# Camera-Switcher.net
KiCad netlist of a schematic drawn in EAGLE
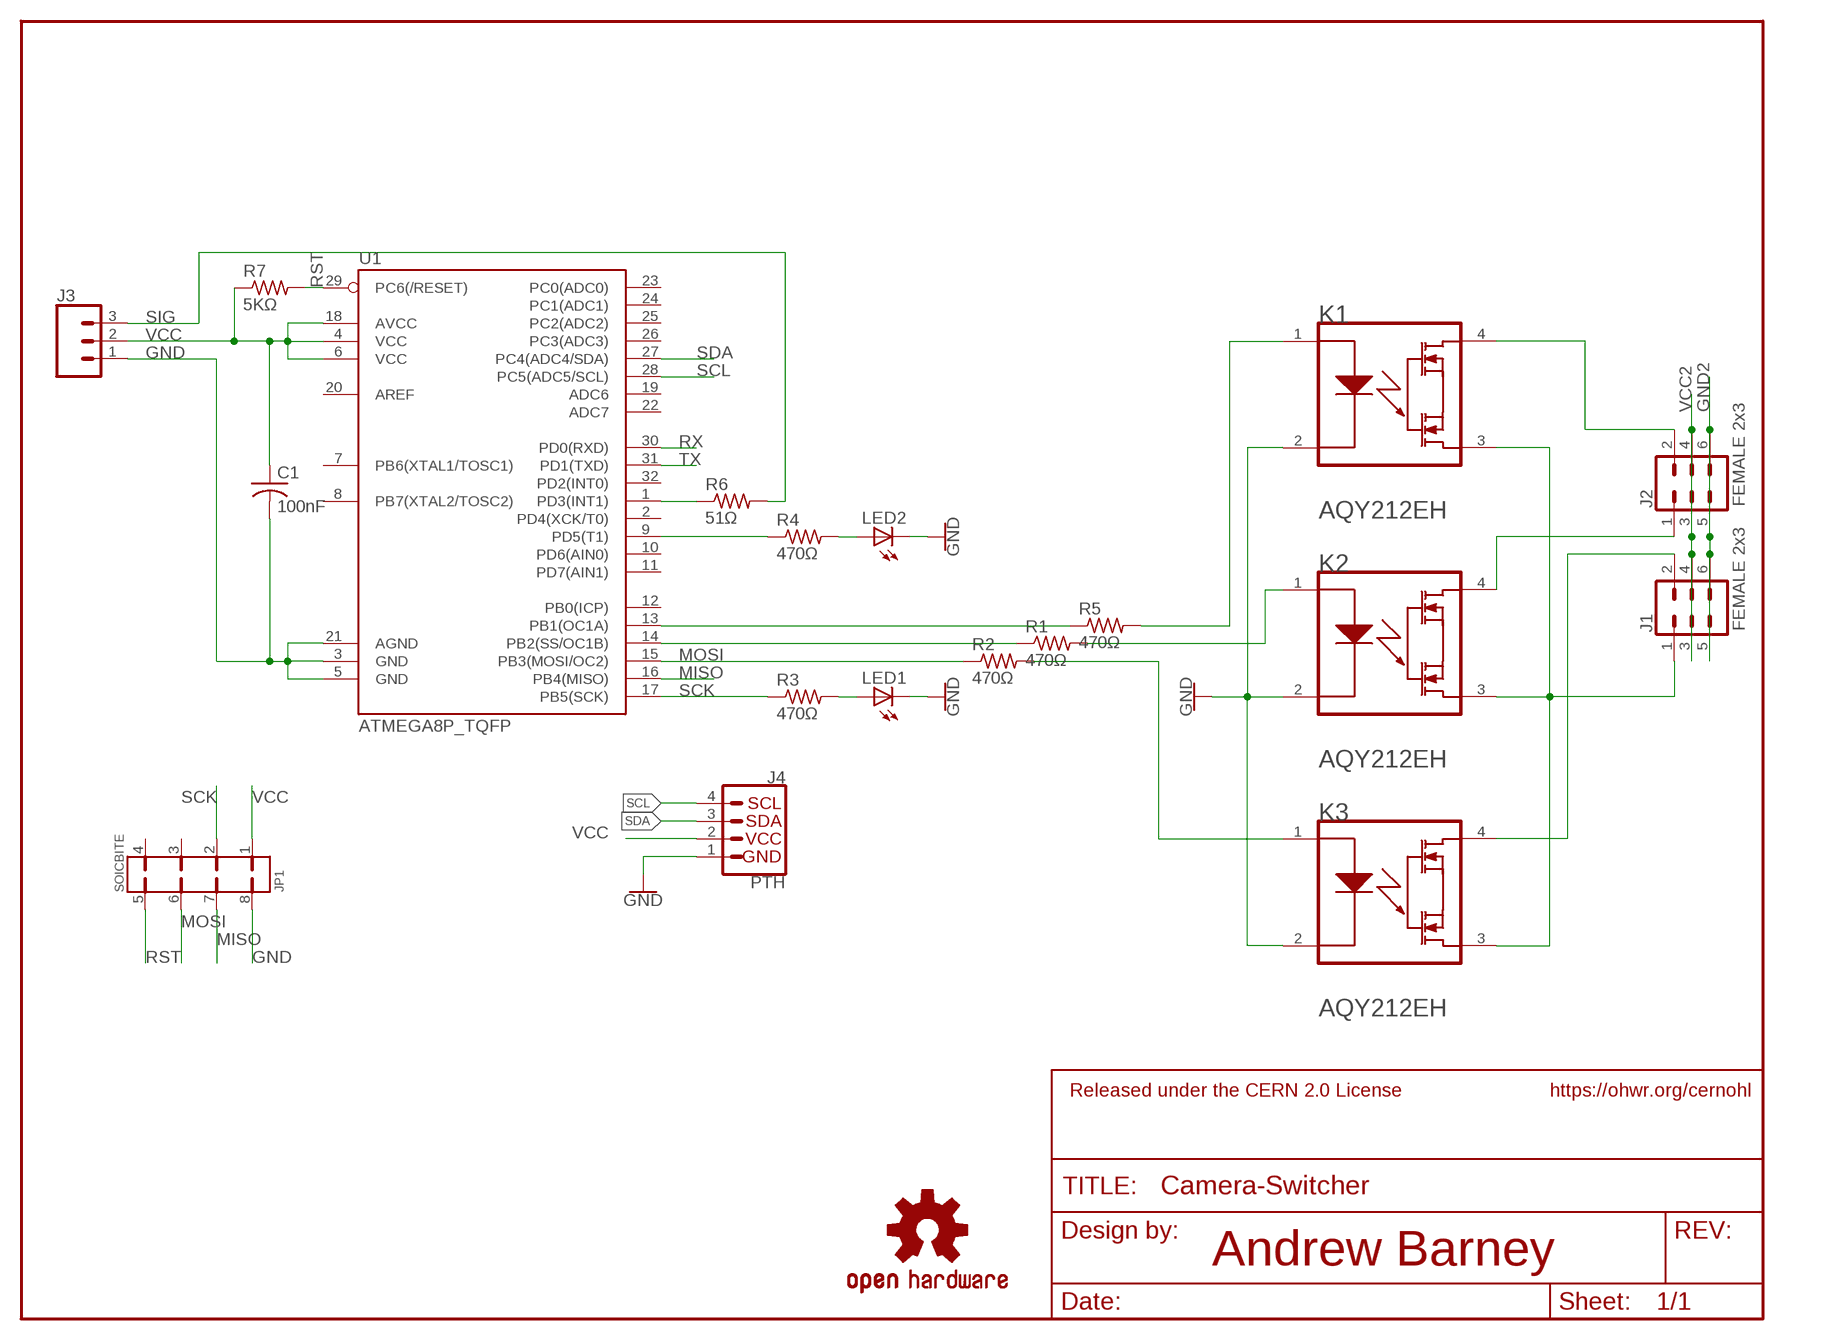
[diagram p0: schematic, sheet 1]

(export (version "E")
  (design (tool "Eeschema 10.0.6"))
  (components
    (comp (ref "C1")
      (value "100nF")
      (footprint "eagle-import:C0805")
      (libsource (lib "eagle-import") (part "C-USC0805"))
    )
    (comp (ref "FRAME1")
      (value "FRAME-LETTER-CERN\"")
      (footprint "eagle-import:CERN-OHL-S")
      (libsource (lib "eagle-import") (part "FRAME-LETTER-CERN{dblquote}"))
    )
    (comp (ref "J1")
      (value "FEMALE 2x3")
      (footprint "eagle-import:2X3")
      (libsource (lib "eagle-import") (part "CONN_03X2FEMALE"))
    )
    (comp (ref "J2")
      (value "FEMALE 2x3")
      (footprint "eagle-import:2X3")
      (libsource (lib "eagle-import") (part "CONN_03X2FEMALE"))
    )
    (comp (ref "J3")
      (value "CONN_03")
      (footprint "eagle-import:1X03")
      (libsource (lib "eagle-import") (part "CONN_03"))
    )
    (comp (ref "J4")
      (value "PTH")
      (footprint "eagle-import:1X04")
      (libsource (lib "eagle-import") (part "I2C_STANDARD"))
    )
    (comp (ref "JP1")
      (value "SOICBITE")
      (footprint "eagle-import:SOICBITE2")
      (libsource (lib "eagle-import") (part "SOICBITE2"))
    )
    (comp (ref "K1")
      (value "PANASONIC_AQY212EHPANASONIC_AQY212EH_0_0")
      (footprint "eagle-import:PANASONIC_AQY212EH_0")
      (fields (field (name "MF") "Panasonic") (field (name "MPN") "AQY212EH"))
      (libsource (lib "eagle-import") (part "PANASONIC_AQY212EHPANASONIC_AQY212EH_0_0"))
    )
    (comp (ref "K2")
      (value "PANASONIC_AQY212EHPANASONIC_AQY212EH_0_0")
      (footprint "eagle-import:PANASONIC_AQY212EH_0")
      (fields (field (name "MF") "Panasonic") (field (name "MPN") "AQY212EH"))
      (libsource (lib "eagle-import") (part "PANASONIC_AQY212EHPANASONIC_AQY212EH_0_0"))
    )
    (comp (ref "K3")
      (value "PANASONIC_AQY212EHPANASONIC_AQY212EH_0_0")
      (footprint "eagle-import:PANASONIC_AQY212EH_0")
      (fields (field (name "MF") "Panasonic") (field (name "MPN") "AQY212EH"))
      (libsource (lib "eagle-import") (part "PANASONIC_AQY212EHPANASONIC_AQY212EH_0_0"))
    )
    (comp (ref "LED1")
      (value "LEDCHIPLED_0805")
      (footprint "eagle-import:CHIPLED_0805")
      (libsource (lib "eagle-import") (part "LEDCHIPLED_0805"))
    )
    (comp (ref "LED2")
      (value "LEDCHIPLED_0805")
      (footprint "eagle-import:CHIPLED_0805")
      (libsource (lib "eagle-import") (part "LEDCHIPLED_0805"))
    )
    (comp (ref "LOGO1")
      (value "OSHW-LOGOS")
      (footprint "eagle-import:OSHW-LOGO-S")
      (libsource (lib "eagle-import") (part "OSHW-LOGOS"))
    )
    (comp (ref "R1")
      (value "470Ω")
      (footprint "eagle-import:R0805")
      (libsource (lib "eagle-import") (part "R-US_R0805"))
    )
    (comp (ref "R2")
      (value "470Ω")
      (footprint "eagle-import:R0805")
      (libsource (lib "eagle-import") (part "R-US_R0805"))
    )
    (comp (ref "R3")
      (value "470Ω")
      (footprint "eagle-import:R0805")
      (libsource (lib "eagle-import") (part "R-US_R0805"))
    )
    (comp (ref "R4")
      (value "470Ω")
      (footprint "eagle-import:R0805")
      (libsource (lib "eagle-import") (part "R-US_R0805"))
    )
    (comp (ref "R5")
      (value "470Ω")
      (footprint "eagle-import:R0805")
      (libsource (lib "eagle-import") (part "R-US_R0805"))
    )
    (comp (ref "R6")
      (value "51Ω")
      (footprint "eagle-import:R0805")
      (libsource (lib "eagle-import") (part "R-US_R0805"))
    )
    (comp (ref "R7")
      (value "5KΩ")
      (footprint "eagle-import:R0805")
      (libsource (lib "eagle-import") (part "R-US_R0805"))
    )
    (comp (ref "U1")
      (value "ATMEGA8P_TQFP")
      (footprint "eagle-import:TQFP32-08")
      (libsource (lib "eagle-import") (part "ATMEGA328P_TQFP"))
    )
  )
  (nets
    (net (code "1") (name "/GND2") (class "Default")
      (node (ref "J1") (pin "5") (pinfunction "5_5") (pintype "bidirectional"))
      (node (ref "J1") (pin "6") (pinfunction "6_6") (pintype "bidirectional"))
      (node (ref "J2") (pin "5") (pinfunction "5_5") (pintype "bidirectional"))
      (node (ref "J2") (pin "6") (pinfunction "6_6") (pintype "bidirectional"))
    )
    (net (code "2") (name "/MISO") (class "Default")
      (node (ref "JP1") (pin "7") (pinfunction "P$7_7") (pintype "passive"))
      (node (ref "U1") (pin "16") (pinfunction "PB4(MISO)_16") (pintype "bidirectional"))
    )
    (net (code "3") (name "/MOSI") (class "Default")
      (node (ref "JP1") (pin "6") (pinfunction "P$6_6") (pintype "passive"))
      (node (ref "R2") (pin "1") (pinfunction "1_1") (pintype "passive"))
      (node (ref "U1") (pin "15") (pinfunction "PB3(MOSI/OC2)_15") (pintype "bidirectional"))
    )
    (net (code "4") (name "/RST") (class "Default")
      (node (ref "JP1") (pin "5") (pinfunction "P$5_5") (pintype "passive"))
      (node (ref "R7") (pin "2") (pinfunction "2_2") (pintype "passive"))
      (node (ref "U1") (pin "29") (pinfunction "PC6(/RESET)_29") (pintype "bidirectional"))
    )
    (net (code "5") (name "/RX") (class "Default")
      (node (ref "U1") (pin "30") (pinfunction "PD0(RXD)_30") (pintype "bidirectional"))
    )
    (net (code "6") (name "/SCK") (class "Default")
      (node (ref "JP1") (pin "2") (pinfunction "P$2_2") (pintype "passive"))
      (node (ref "R3") (pin "1") (pinfunction "1_1") (pintype "passive"))
      (node (ref "U1") (pin "17") (pinfunction "PB5(SCK)_17") (pintype "bidirectional"))
    )
    (net (code "7") (name "/SIG") (class "Default")
      (node (ref "J3") (pin "3") (pinfunction "3_3") (pintype "passive"))
      (node (ref "R6") (pin "2") (pinfunction "2_2") (pintype "passive"))
    )
    (net (code "8") (name "/TX") (class "Default")
      (node (ref "U1") (pin "31") (pinfunction "PD1(TXD)_31") (pintype "bidirectional"))
    )
    (net (code "9") (name "/VCC") (class "Default")
      (node (ref "C1") (pin "1") (pinfunction "1_1") (pintype "passive"))
      (node (ref "J3") (pin "2") (pinfunction "2_2") (pintype "passive"))
      (node (ref "J4") (pin "2") (pinfunction "2_2") (pintype "power_in"))
      (node (ref "JP1") (pin "1") (pinfunction "P$1_1") (pintype "passive"))
      (node (ref "R7") (pin "1") (pinfunction "1_1") (pintype "passive"))
      (node (ref "U1") (pin "18") (pinfunction "AVCC_18") (pintype "bidirectional"))
      (node (ref "U1") (pin "4") (pinfunction "VCC_4") (pintype "bidirectional"))
      (node (ref "U1") (pin "6") (pinfunction "VCC_6") (pintype "bidirectional"))
    )
    (net (code "10") (name "/VCC2") (class "Default")
      (node (ref "J1") (pin "3") (pinfunction "3_3") (pintype "bidirectional"))
      (node (ref "J1") (pin "4") (pinfunction "4_4") (pintype "bidirectional"))
      (node (ref "J2") (pin "3") (pinfunction "3_3") (pintype "bidirectional"))
      (node (ref "J2") (pin "4") (pinfunction "4_4") (pintype "bidirectional"))
    )
    (net (code "11") (name "GND") (class "Default")
      (node (ref "C1") (pin "2") (pinfunction "2_2") (pintype "passive"))
      (node (ref "J3") (pin "1") (pinfunction "1_1") (pintype "passive"))
      (node (ref "J4") (pin "1") (pinfunction "1_1") (pintype "power_in"))
      (node (ref "JP1") (pin "8") (pinfunction "P$8_8") (pintype "passive"))
      (node (ref "K1") (pin "2") (pinfunction "2_2") (pintype "passive"))
      (node (ref "K2") (pin "2") (pinfunction "2_2") (pintype "passive"))
      (node (ref "K3") (pin "2") (pinfunction "2_2") (pintype "passive"))
      (node (ref "LED1") (pin "C") (pinfunction "C_C") (pintype "passive"))
      (node (ref "LED2") (pin "C") (pinfunction "C_C") (pintype "passive"))
      (node (ref "U1") (pin "21") (pinfunction "AGND_21") (pintype "bidirectional"))
      (node (ref "U1") (pin "3") (pinfunction "GND_3") (pintype "bidirectional"))
      (node (ref "U1") (pin "5") (pinfunction "GND_5") (pintype "bidirectional"))
    )
    (net (code "12") (name "Net-(J1-Pad1)") (class "Default")
      (node (ref "J1") (pin "1") (pinfunction "1_1") (pintype "bidirectional"))
      (node (ref "K1") (pin "3") (pinfunction "3_3") (pintype "passive"))
      (node (ref "K2") (pin "3") (pinfunction "3_3") (pintype "passive"))
      (node (ref "K3") (pin "3") (pinfunction "3_3") (pintype "passive"))
    )
    (net (code "13") (name "Net-(J1-Pad2)") (class "Default")
      (node (ref "J1") (pin "2") (pinfunction "2_2") (pintype "bidirectional"))
      (node (ref "K3") (pin "4") (pinfunction "4_4") (pintype "passive"))
    )
    (net (code "14") (name "Net-(J2-Pad1)") (class "Default")
      (node (ref "J2") (pin "1") (pinfunction "1_1") (pintype "bidirectional"))
      (node (ref "K2") (pin "4") (pinfunction "4_4") (pintype "passive"))
    )
    (net (code "15") (name "Net-(J2-Pad2)") (class "Default")
      (node (ref "J2") (pin "2") (pinfunction "2_2") (pintype "bidirectional"))
      (node (ref "K1") (pin "4") (pinfunction "4_4") (pintype "passive"))
    )
    (net (code "16") (name "Net-(K1-Pad1)") (class "Default")
      (node (ref "K1") (pin "1") (pinfunction "1_1") (pintype "passive"))
      (node (ref "R5") (pin "2") (pinfunction "2_2") (pintype "passive"))
    )
    (net (code "17") (name "Net-(K2-Pad1)") (class "Default")
      (node (ref "K2") (pin "1") (pinfunction "1_1") (pintype "passive"))
      (node (ref "R1") (pin "2") (pinfunction "2_2") (pintype "passive"))
    )
    (net (code "18") (name "Net-(K3-Pad1)") (class "Default")
      (node (ref "K3") (pin "1") (pinfunction "1_1") (pintype "passive"))
      (node (ref "R2") (pin "2") (pinfunction "2_2") (pintype "passive"))
    )
    (net (code "19") (name "Net-(LED1-PadA)") (class "Default")
      (node (ref "LED1") (pin "A") (pinfunction "A_A") (pintype "passive"))
      (node (ref "R3") (pin "2") (pinfunction "2_2") (pintype "passive"))
    )
    (net (code "20") (name "Net-(LED2-PadA)") (class "Default")
      (node (ref "LED2") (pin "A") (pinfunction "A_A") (pintype "passive"))
      (node (ref "R4") (pin "2") (pinfunction "2_2") (pintype "passive"))
    )
    (net (code "21") (name "Net-(U1-PB1(OC1A))") (class "Default")
      (node (ref "R5") (pin "1") (pinfunction "1_1") (pintype "passive"))
      (node (ref "U1") (pin "13") (pinfunction "PB1(OC1A)_13") (pintype "bidirectional"))
    )
    (net (code "22") (name "Net-(U1-PB2(SS{slash}OC1B))") (class "Default")
      (node (ref "R1") (pin "1") (pinfunction "1_1") (pintype "passive"))
      (node (ref "U1") (pin "14") (pinfunction "PB2(SS/OC1B)_14") (pintype "bidirectional"))
    )
    (net (code "23") (name "Net-(U1-PD3(INT1))") (class "Default")
      (node (ref "R6") (pin "1") (pinfunction "1_1") (pintype "passive"))
      (node (ref "U1") (pin "1") (pinfunction "PD3(INT1)_1") (pintype "bidirectional"))
    )
    (net (code "24") (name "Net-(U1-PD5(T1))") (class "Default")
      (node (ref "R4") (pin "1") (pinfunction "1_1") (pintype "passive"))
      (node (ref "U1") (pin "9") (pinfunction "PD5(T1)_9") (pintype "bidirectional"))
    )
    (net (code "25") (name "SCL") (class "Default")
      (node (ref "J4") (pin "4") (pinfunction "4_4") (pintype "passive"))
      (node (ref "U1") (pin "28") (pinfunction "PC5(ADC5/SCL)_28") (pintype "bidirectional"))
    )
    (net (code "26") (name "SDA") (class "Default")
      (node (ref "J4") (pin "3") (pinfunction "3_3") (pintype "passive"))
      (node (ref "U1") (pin "27") (pinfunction "PC4(ADC4/SDA)_27") (pintype "bidirectional"))
    )
    (net (code "27") (name "unconnected-(JP1-P$3-Pad3)") (class "Default")
      (node (ref "JP1") (pin "3") (pinfunction "P$3_3") (pintype "passive"))
    )
    (net (code "28") (name "unconnected-(JP1-P$4-Pad4)") (class "Default")
      (node (ref "JP1") (pin "4") (pinfunction "P$4_4") (pintype "passive"))
    )
    (net (code "29") (name "unconnected-(U1-ADC6-Pad19)") (class "Default")
      (node (ref "U1") (pin "19") (pinfunction "ADC6_19") (pintype "bidirectional"))
    )
    (net (code "30") (name "unconnected-(U1-ADC7-Pad22)") (class "Default")
      (node (ref "U1") (pin "22") (pinfunction "ADC7_22") (pintype "bidirectional"))
    )
    (net (code "31") (name "unconnected-(U1-AREF-Pad20)") (class "Default")
      (node (ref "U1") (pin "20") (pinfunction "AREF_20") (pintype "bidirectional"))
    )
    (net (code "32") (name "unconnected-(U1-PB0(ICP)-Pad12)") (class "Default")
      (node (ref "U1") (pin "12") (pinfunction "PB0(ICP)_12") (pintype "bidirectional"))
    )
    (net (code "33") (name "unconnected-(U1-PB6(XTAL1{slash}TOSC1)-Pad7)") (class "Default")
      (node (ref "U1") (pin "7") (pinfunction "PB6(XTAL1/TOSC1)_7") (pintype "bidirectional"))
    )
    (net (code "34") (name "unconnected-(U1-PB7(XTAL2{slash}TOSC2)-Pad8)") (class "Default")
      (node (ref "U1") (pin "8") (pinfunction "PB7(XTAL2/TOSC2)_8") (pintype "bidirectional"))
    )
    (net (code "35") (name "unconnected-(U1-PC0(ADC0)-Pad23)") (class "Default")
      (node (ref "U1") (pin "23") (pinfunction "PC0(ADC0)_23") (pintype "bidirectional"))
    )
    (net (code "36") (name "unconnected-(U1-PC1(ADC1)-Pad24)") (class "Default")
      (node (ref "U1") (pin "24") (pinfunction "PC1(ADC1)_24") (pintype "bidirectional"))
    )
    (net (code "37") (name "unconnected-(U1-PC2(ADC2)-Pad25)") (class "Default")
      (node (ref "U1") (pin "25") (pinfunction "PC2(ADC2)_25") (pintype "bidirectional"))
    )
    (net (code "38") (name "unconnected-(U1-PC3(ADC3)-Pad26)") (class "Default")
      (node (ref "U1") (pin "26") (pinfunction "PC3(ADC3)_26") (pintype "bidirectional"))
    )
    (net (code "39") (name "unconnected-(U1-PD2(INT0)-Pad32)") (class "Default")
      (node (ref "U1") (pin "32") (pinfunction "PD2(INT0)_32") (pintype "bidirectional"))
    )
    (net (code "40") (name "unconnected-(U1-PD4(XCK{slash}T0)-Pad2)") (class "Default")
      (node (ref "U1") (pin "2") (pinfunction "PD4(XCK/T0)_2") (pintype "bidirectional"))
    )
    (net (code "41") (name "unconnected-(U1-PD6(AIN0)-Pad10)") (class "Default")
      (node (ref "U1") (pin "10") (pinfunction "PD6(AIN0)_10") (pintype "bidirectional"))
    )
    (net (code "42") (name "unconnected-(U1-PD7(AIN1)-Pad11)") (class "Default")
      (node (ref "U1") (pin "11") (pinfunction "PD7(AIN1)_11") (pintype "bidirectional"))
    )
  )
)
